# V-00724-00.net
KiCad netlist of a schematic drawn in EAGLE
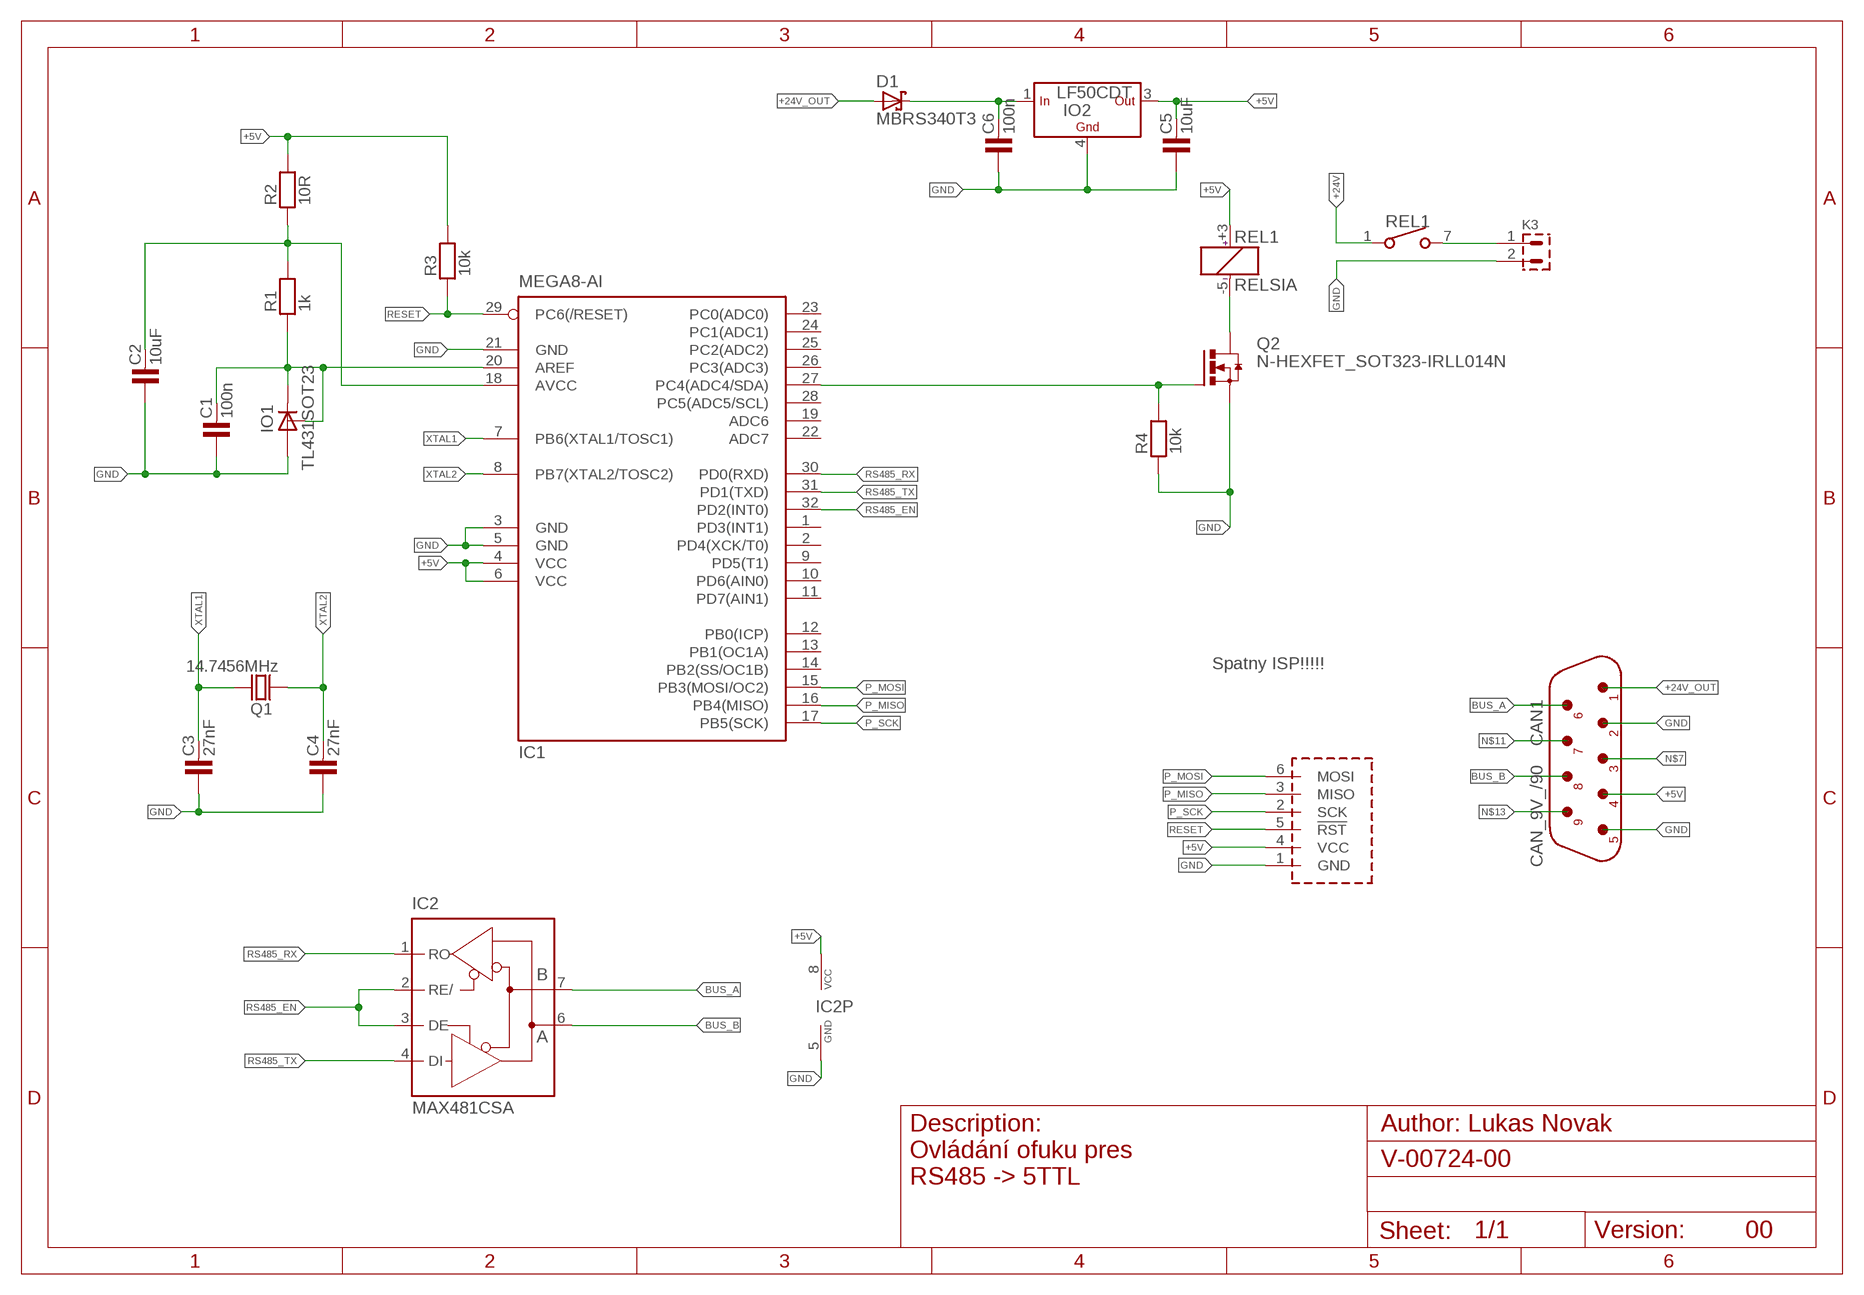
[diagram p0: schematic, sheet 1]

(export (version "E")
  (design (tool "Eeschema 10.0.6"))
  (components
    (comp (ref "C1")
      (value "100n")
      (footprint "eagle-import:1206")
      (libsource (lib "eagle-import") (part "C-KER_1206"))
    )
    (comp (ref "C2")
      (value "10uF")
      (footprint "eagle-import:1206")
      (libsource (lib "eagle-import") (part "C-KER_1206"))
    )
    (comp (ref "C3")
      (value "27nF")
      (footprint "eagle-import:0805")
      (libsource (lib "eagle-import") (part "C-KER_0805"))
    )
    (comp (ref "C4")
      (value "27nF")
      (footprint "eagle-import:0805")
      (libsource (lib "eagle-import") (part "C-KER_0805"))
    )
    (comp (ref "C5")
      (value "10uF")
      (footprint "eagle-import:1206")
      (libsource (lib "eagle-import") (part "C-KER_1206"))
    )
    (comp (ref "C6")
      (value "100n")
      (footprint "eagle-import:1206")
      (libsource (lib "eagle-import") (part "C-KER_1206"))
    )
    (comp (ref "CAN1")
      (value "CAN_9V_/90")
      (footprint "eagle-import:CAN9V_90")
      (libsource (lib "eagle-import") (part "CAN_9V_/90"))
    )
    (comp (ref "D1")
      (value "MBRS340T3")
      (footprint "eagle-import:SMC")
      (libsource (lib "eagle-import") (part "MBRS30T34"))
    )
    (comp (ref "IC1")
      (value "MEGA8-AI")
      (footprint "eagle-import:TQFP32-08")
      (fields (field (name "MPN") "ATMEGA8-16AU"))
      (libsource (lib "eagle-import") (part "MEGA8-AI"))
    )
    (comp (ref "IC2")
      (value "MAX481CSA")
      (footprint "eagle-import:SO08")
      (fields (field (name "MF") "MAXIM"))
      (libsource (lib "eagle-import") (part "MAX481CSA"))
    )
    (comp (ref "IO1")
      (value "TL431SOT23")
      (footprint "eagle-import:SOT23")
      (fields (field (name "MPN") "TL431BFDT"))
      (libsource (lib "eagle-import") (part "TL431SOT23"))
    )
    (comp (ref "IO2")
      (value "LF50CDT")
      (footprint "eagle-import:DPAK")
      (libsource (lib "eagle-import") (part "LF_CDT"))
    )
    (comp (ref "K3")
      (value "PSH02-02P")
      (footprint "eagle-import:PSH02-02P")
      (libsource (lib "eagle-import") (part "PSH02-02P"))
    )
    (comp (ref "Q1")
      (value "14.7456MHz")
      (footprint "eagle-import:HC-49U")
      (libsource (lib "eagle-import") (part "Q_HC-49U"))
    )
    (comp (ref "Q2")
      (value "N-HEXFET_SOT323-IRLL014N")
      (footprint "eagle-import:SOT223")
      (libsource (lib "eagle-import") (part "N-HEXFET_?-SOT323IRLL014N"))
    )
    (comp (ref "R1")
      (value "1k")
      (footprint "eagle-import:1206")
      (libsource (lib "eagle-import") (part "R_1206"))
    )
    (comp (ref "R2")
      (value "10R")
      (footprint "eagle-import:1206")
      (libsource (lib "eagle-import") (part "R_1206"))
    )
    (comp (ref "R3")
      (value "10k")
      (footprint "eagle-import:1206")
      (libsource (lib "eagle-import") (part "R_1206"))
    )
    (comp (ref "R4")
      (value "10k")
      (footprint "eagle-import:1206")
      (libsource (lib "eagle-import") (part "R_1206"))
    )
    (comp (ref "REL1")
      (value "RELSIA")
      (footprint "eagle-import:RELSIA")
      (libsource (lib "eagle-import") (part "RELSIA??"))
    )
    (comp (ref "U$1")
      (value "AVR_PROG_SPI")
      (footprint "eagle-import:PSH02-06P")
      (libsource (lib "eagle-import") (part "AVR_PROG_SPI"))
    )
  )
  (nets
    (net (code "1") (name "+5V") (class "Default")
      (node (ref "C5") (pin "2") (pinfunction "2_2") (pintype "passive"))
      (node (ref "CAN1") (pin "4") (pinfunction "4_4") (pintype "passive"))
      (node (ref "IC1") (pin "4") (pinfunction "VCC_4") (pintype "power_in"))
      (node (ref "IC1") (pin "6") (pinfunction "VCC_6") (pintype "power_in"))
      (node (ref "IC2") (pin "8") (pinfunction "VCC_8") (pintype "power_in"))
      (node (ref "IO2") (pin "3") (pinfunction "OUT_3") (pintype "passive"))
      (node (ref "R2") (pin "2") (pinfunction "2_2") (pintype "passive"))
      (node (ref "R3") (pin "2") (pinfunction "2_2") (pintype "passive"))
      (node (ref "REL1") (pin "+3") (pinfunction "C+_+3") (pintype "passive"))
      (node (ref "U$1") (pin "4") (pinfunction "VCC_4") (pintype "bidirectional"))
    )
    (net (code "2") (name "+24V") (class "Default")
      (node (ref "C6") (pin "2") (pinfunction "2_2") (pintype "passive"))
      (node (ref "D1") (pin "C") (pinfunction "C_C") (pintype "passive"))
      (node (ref "IO2") (pin "1") (pinfunction "IN_1") (pintype "passive"))
      (node (ref "REL1") (pin "1") (pinfunction "1_1") (pintype "passive"))
    )
    (net (code "3") (name "+24V_OUT") (class "Default")
      (node (ref "CAN1") (pin "1") (pinfunction "1_1") (pintype "passive"))
      (node (ref "D1") (pin "A") (pinfunction "A_A") (pintype "passive"))
    )
    (net (code "4") (name "BUS_A") (class "Default")
      (node (ref "CAN1") (pin "6") (pinfunction "6_6") (pintype "passive"))
      (node (ref "IC2") (pin "7") (pinfunction "B_7") (pintype "passive"))
    )
    (net (code "5") (name "BUS_B") (class "Default")
      (node (ref "CAN1") (pin "8") (pinfunction "8_8") (pintype "passive"))
      (node (ref "IC2") (pin "6") (pinfunction "A_6") (pintype "passive"))
    )
    (net (code "6") (name "GND") (class "Default")
      (node (ref "C1") (pin "1") (pinfunction "1_1") (pintype "passive"))
      (node (ref "C2") (pin "1") (pinfunction "1_1") (pintype "passive"))
      (node (ref "C3") (pin "1") (pinfunction "1_1") (pintype "passive"))
      (node (ref "C4") (pin "1") (pinfunction "1_1") (pintype "passive"))
      (node (ref "C5") (pin "1") (pinfunction "1_1") (pintype "passive"))
      (node (ref "C6") (pin "1") (pinfunction "1_1") (pintype "passive"))
      (node (ref "CAN1") (pin "2") (pinfunction "2_2") (pintype "passive"))
      (node (ref "CAN1") (pin "5") (pinfunction "5_5") (pintype "passive"))
      (node (ref "IC1") (pin "21") (pinfunction "GND_21") (pintype "power_in"))
      (node (ref "IC1") (pin "3") (pinfunction "GND_3") (pintype "power_in"))
      (node (ref "IC1") (pin "5") (pinfunction "GND_5") (pintype "power_in"))
      (node (ref "IC2") (pin "5") (pinfunction "GND_5") (pintype "power_in"))
      (node (ref "IO1") (pin "3") (pinfunction "A_3") (pintype "bidirectional"))
      (node (ref "IO2") (pin "4") (pinfunction "GND_4") (pintype "passive"))
      (node (ref "K3") (pin "2") (pinfunction "2_2") (pintype "passive"))
      (node (ref "Q2") (pin "3") (pinfunction "S_3") (pintype "passive"))
      (node (ref "R4") (pin "1") (pinfunction "1_1") (pintype "passive"))
      (node (ref "U$1") (pin "1") (pinfunction "GND_1") (pintype "bidirectional"))
    )
    (net (code "7") (name "N$7") (class "Default")
      (node (ref "CAN1") (pin "3") (pinfunction "3_3") (pintype "passive"))
    )
    (net (code "8") (name "N$11") (class "Default")
      (node (ref "CAN1") (pin "7") (pinfunction "7_7") (pintype "passive"))
    )
    (net (code "9") (name "N$13") (class "Default")
      (node (ref "CAN1") (pin "9") (pinfunction "9_9") (pintype "passive"))
    )
    (net (code "10") (name "Net-(IC1-AREF)") (class "Default")
      (node (ref "C1") (pin "2") (pinfunction "2_2") (pintype "passive"))
      (node (ref "IC1") (pin "20") (pinfunction "AREF_20") (pintype "passive"))
      (node (ref "IO1") (pin "1") (pinfunction "C_1") (pintype "bidirectional"))
      (node (ref "IO1") (pin "2") (pinfunction "R_2") (pintype "bidirectional"))
      (node (ref "R1") (pin "1") (pinfunction "1_1") (pintype "passive"))
    )
    (net (code "11") (name "Net-(IC1-AVCC)") (class "Default")
      (node (ref "C2") (pin "2") (pinfunction "2_2") (pintype "passive"))
      (node (ref "IC1") (pin "18") (pinfunction "AVCC_18") (pintype "power_in"))
      (node (ref "R1") (pin "2") (pinfunction "2_2") (pintype "passive"))
      (node (ref "R2") (pin "1") (pinfunction "1_1") (pintype "passive"))
    )
    (net (code "12") (name "Net-(IC1-PC4(ADC4{slash}SDA))") (class "Default")
      (node (ref "IC1") (pin "27") (pinfunction "PC4(ADC4/SDA)_27") (pintype "bidirectional"))
      (node (ref "Q2") (pin "1") (pinfunction "G_1") (pintype "passive"))
      (node (ref "R4") (pin "2") (pinfunction "2_2") (pintype "passive"))
    )
    (net (code "13") (name "Net-(Q2-D)") (class "Default")
      (node (ref "Q2") (pin "4") (pinfunction "D_4") (pintype "passive"))
      (node (ref "REL1") (pin "-5") (pinfunction "C-_-5") (pintype "passive"))
    )
    (net (code "14") (name "Net-(REL1B-2)") (class "Default")
      (node (ref "K3") (pin "1") (pinfunction "1_1") (pintype "passive"))
      (node (ref "REL1") (pin "7") (pinfunction "2_7") (pintype "passive"))
    )
    (net (code "15") (name "P_MISO") (class "Default")
      (node (ref "IC1") (pin "16") (pinfunction "PB4(MISO)_16") (pintype "bidirectional"))
      (node (ref "U$1") (pin "3") (pinfunction "MISO_3") (pintype "bidirectional"))
    )
    (net (code "16") (name "P_MOSI") (class "Default")
      (node (ref "IC1") (pin "15") (pinfunction "PB3(MOSI/OC2)_15") (pintype "bidirectional"))
      (node (ref "U$1") (pin "6") (pinfunction "MOSI_6") (pintype "bidirectional"))
    )
    (net (code "17") (name "P_SCK") (class "Default")
      (node (ref "IC1") (pin "17") (pinfunction "PB5(SCK)_17") (pintype "bidirectional"))
      (node (ref "U$1") (pin "2") (pinfunction "SCK_2") (pintype "bidirectional"))
    )
    (net (code "18") (name "RESET") (class "Default")
      (node (ref "IC1") (pin "29") (pinfunction "PC6(/RESET)_29") (pintype "bidirectional"))
      (node (ref "R3") (pin "1") (pinfunction "1_1") (pintype "passive"))
      (node (ref "U$1") (pin "5") (pinfunction "~{RST}_5") (pintype "bidirectional"))
    )
    (net (code "19") (name "RS485_EN") (class "Default")
      (node (ref "IC1") (pin "32") (pinfunction "PD2(INT0)_32") (pintype "bidirectional"))
      (node (ref "IC2") (pin "2") (pinfunction "RE/_2") (pintype "input"))
      (node (ref "IC2") (pin "3") (pinfunction "DE_3") (pintype "input"))
    )
    (net (code "20") (name "RS485_RX") (class "Default")
      (node (ref "IC1") (pin "30") (pinfunction "PD0(RXD)_30") (pintype "bidirectional"))
      (node (ref "IC2") (pin "1") (pinfunction "RO_1") (pintype "output"))
    )
    (net (code "21") (name "RS485_TX") (class "Default")
      (node (ref "IC1") (pin "31") (pinfunction "PD1(TXD)_31") (pintype "bidirectional"))
      (node (ref "IC2") (pin "4") (pinfunction "DI_4") (pintype "input"))
    )
    (net (code "22") (name "XTAL1") (class "Default")
      (node (ref "C3") (pin "2") (pinfunction "2_2") (pintype "passive"))
      (node (ref "IC1") (pin "7") (pinfunction "PB6(XTAL1/TOSC1)_7") (pintype "bidirectional"))
      (node (ref "Q1") (pin "2") (pinfunction "2_2") (pintype "passive"))
    )
    (net (code "23") (name "XTAL2") (class "Default")
      (node (ref "C4") (pin "2") (pinfunction "2_2") (pintype "passive"))
      (node (ref "IC1") (pin "8") (pinfunction "PB7(XTAL2/TOSC2)_8") (pintype "bidirectional"))
      (node (ref "Q1") (pin "1") (pinfunction "1_1") (pintype "passive"))
    )
    (net (code "24") (name "unconnected-(IC1-ADC6-Pad19)") (class "Default")
      (node (ref "IC1") (pin "19") (pinfunction "ADC6_19") (pintype "bidirectional"))
    )
    (net (code "25") (name "unconnected-(IC1-ADC7-Pad22)") (class "Default")
      (node (ref "IC1") (pin "22") (pinfunction "ADC7_22") (pintype "bidirectional"))
    )
    (net (code "26") (name "unconnected-(IC1-PB0(ICP)-Pad12)") (class "Default")
      (node (ref "IC1") (pin "12") (pinfunction "PB0(ICP)_12") (pintype "bidirectional"))
    )
    (net (code "27") (name "unconnected-(IC1-PB1(OC1A)-Pad13)") (class "Default")
      (node (ref "IC1") (pin "13") (pinfunction "PB1(OC1A)_13") (pintype "bidirectional"))
    )
    (net (code "28") (name "unconnected-(IC1-PB2(SS{slash}OC1B)-Pad14)") (class "Default")
      (node (ref "IC1") (pin "14") (pinfunction "PB2(SS/OC1B)_14") (pintype "bidirectional"))
    )
    (net (code "29") (name "unconnected-(IC1-PC0(ADC0)-Pad23)") (class "Default")
      (node (ref "IC1") (pin "23") (pinfunction "PC0(ADC0)_23") (pintype "bidirectional"))
    )
    (net (code "30") (name "unconnected-(IC1-PC1(ADC1)-Pad24)") (class "Default")
      (node (ref "IC1") (pin "24") (pinfunction "PC1(ADC1)_24") (pintype "bidirectional"))
    )
    (net (code "31") (name "unconnected-(IC1-PC2(ADC2)-Pad25)") (class "Default")
      (node (ref "IC1") (pin "25") (pinfunction "PC2(ADC2)_25") (pintype "bidirectional"))
    )
    (net (code "32") (name "unconnected-(IC1-PC3(ADC3)-Pad26)") (class "Default")
      (node (ref "IC1") (pin "26") (pinfunction "PC3(ADC3)_26") (pintype "bidirectional"))
    )
    (net (code "33") (name "unconnected-(IC1-PC5(ADC5{slash}SCL)-Pad28)") (class "Default")
      (node (ref "IC1") (pin "28") (pinfunction "PC5(ADC5/SCL)_28") (pintype "bidirectional"))
    )
    (net (code "34") (name "unconnected-(IC1-PD3(INT1)-Pad1)") (class "Default")
      (node (ref "IC1") (pin "1") (pinfunction "PD3(INT1)_1") (pintype "bidirectional"))
    )
    (net (code "35") (name "unconnected-(IC1-PD4(XCK{slash}T0)-Pad2)") (class "Default")
      (node (ref "IC1") (pin "2") (pinfunction "PD4(XCK/T0)_2") (pintype "bidirectional"))
    )
    (net (code "36") (name "unconnected-(IC1-PD5(T1)-Pad9)") (class "Default")
      (node (ref "IC1") (pin "9") (pinfunction "PD5(T1)_9") (pintype "bidirectional"))
    )
    (net (code "37") (name "unconnected-(IC1-PD6(AIN0)-Pad10)") (class "Default")
      (node (ref "IC1") (pin "10") (pinfunction "PD6(AIN0)_10") (pintype "bidirectional"))
    )
    (net (code "38") (name "unconnected-(IC1-PD7(AIN1)-Pad11)") (class "Default")
      (node (ref "IC1") (pin "11") (pinfunction "PD7(AIN1)_11") (pintype "bidirectional"))
    )
  )
)
